# top.net
KiCad netlist of a schematic drawn in Altium Designer
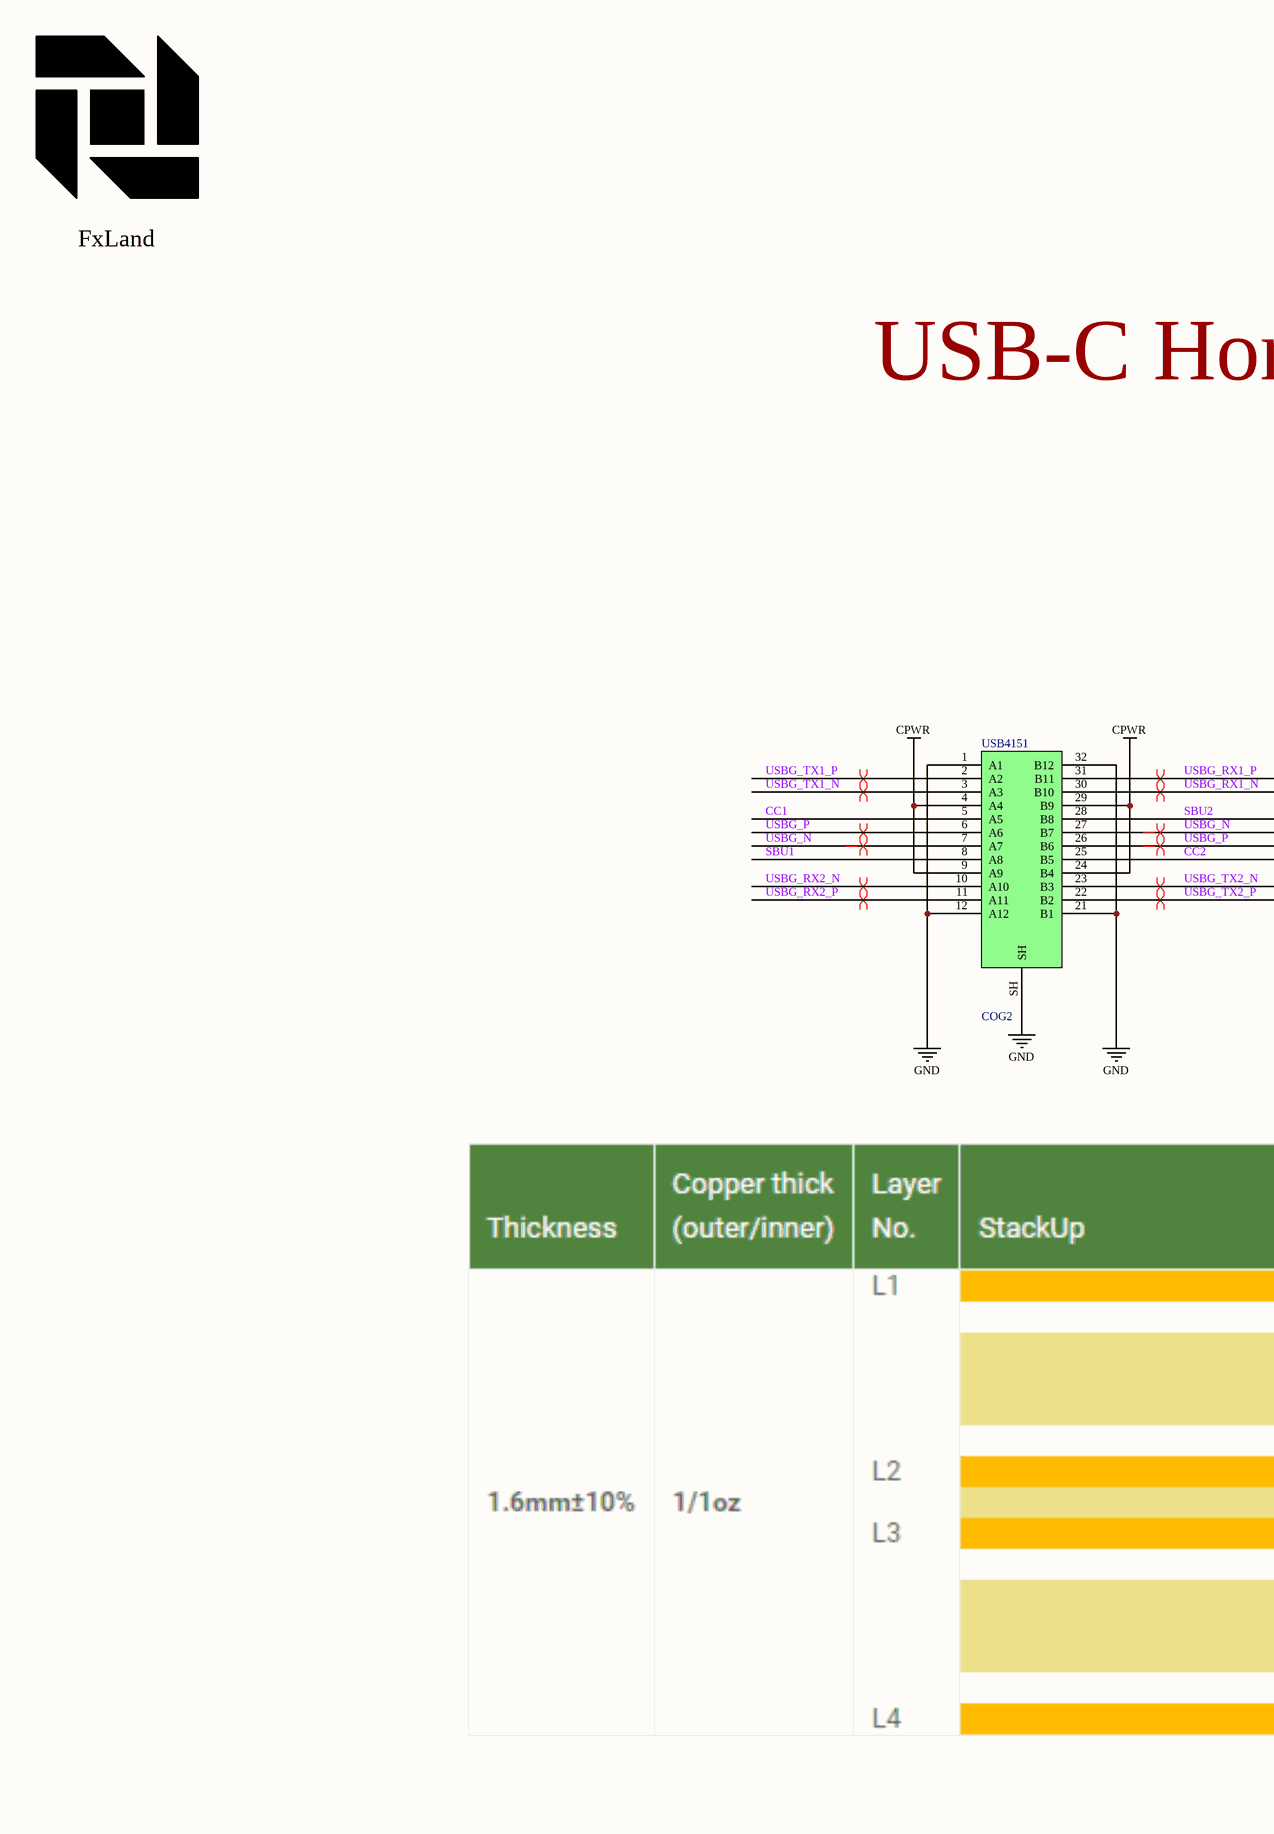
[diagram p0: top.SchDoc, left]
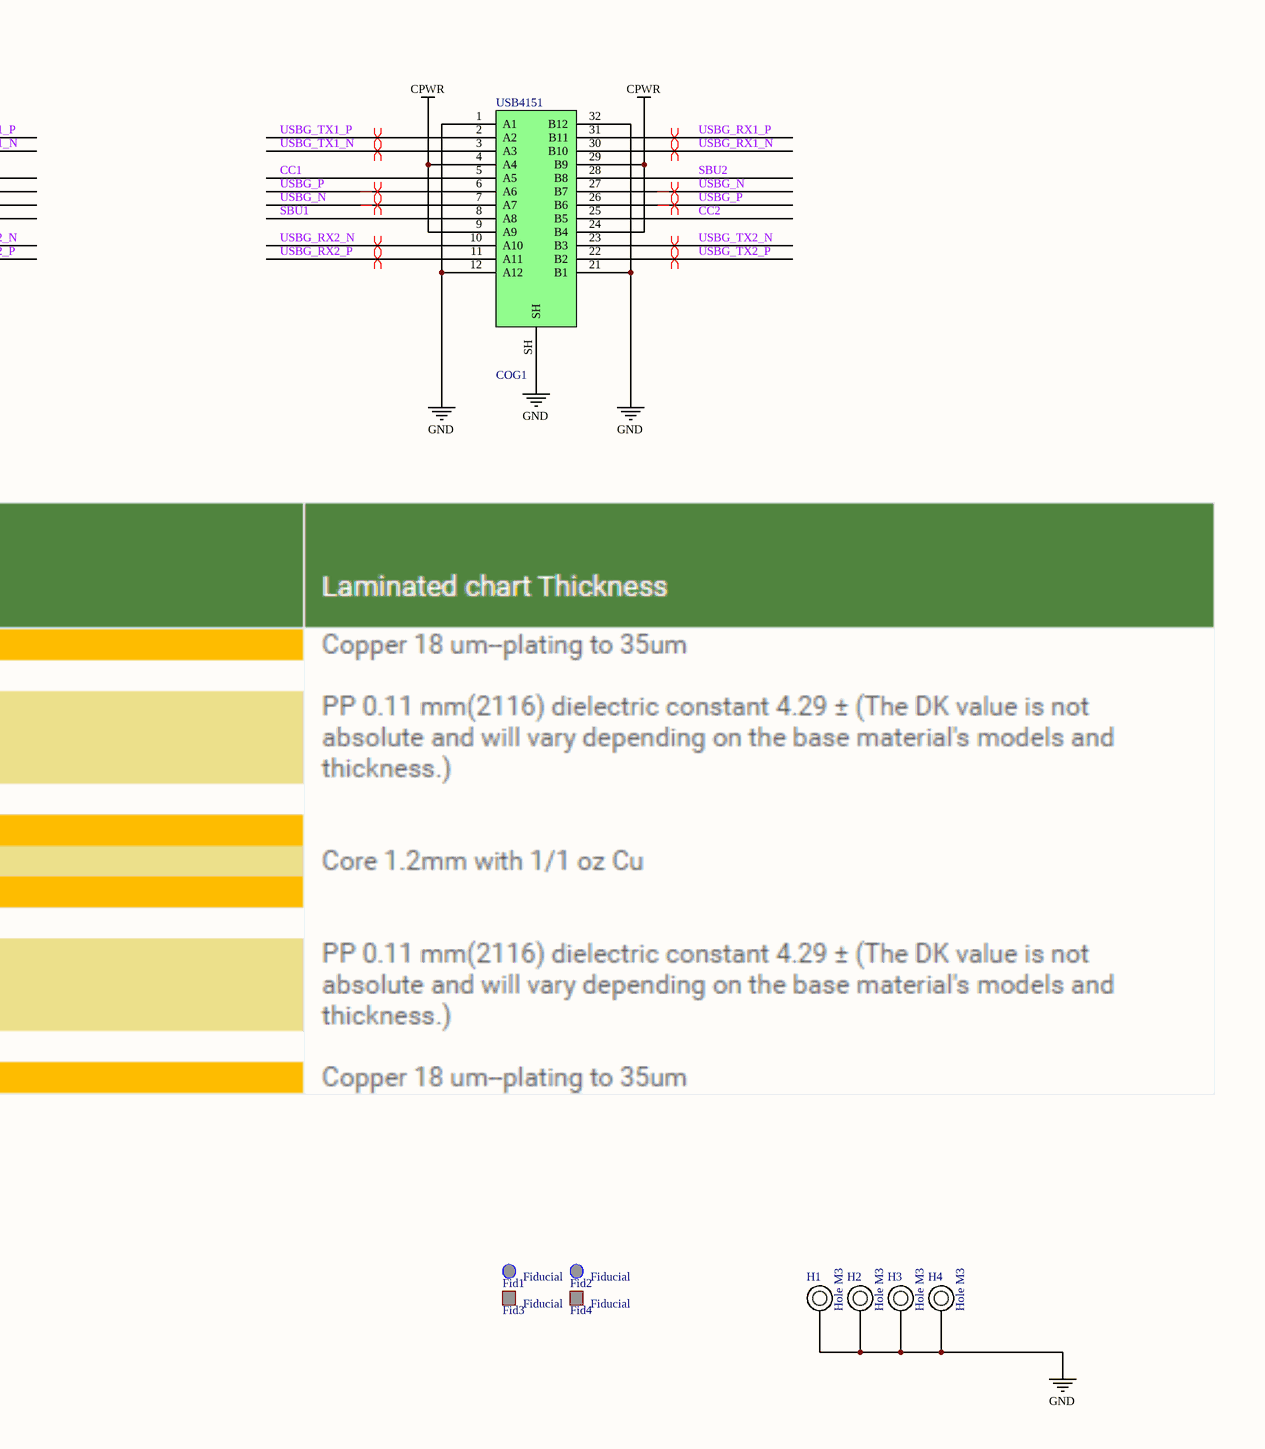
[diagram p1: top.SchDoc, right]

(export (version "E")
  (design (tool "Eeschema 10.0.6"))
  (components
    (comp (ref "COG1")
      (value "USB4151")
      (footprint "USB4151-GF-C")
      (description "USB C connector Plug")
      (fields
        (field (name "REFVAL") "USB4151")
        (field (name "PART NUMBER") "CO0017")
        (field (name "MANFACTPART") "USB4151-GF-C")
      )
      (libsource (lib "GTS_Database") (part "USB-CC"))
    )
    (comp (ref "COG2")
      (value "USB4151")
      (footprint "USB4151-GF-C")
      (description "USB C connector Plug")
      (fields
        (field (name "REFVAL") "USB4151")
        (field (name "PART NUMBER") "CO0017")
        (field (name "MANFACTPART") "USB4151-GF-C")
      )
      (libsource (lib "GTS_Database") (part "USB-CC"))
    )
    (comp (ref "Fid1")
      (value "Fiducial")
      (footprint "FidR_1.0mm")
      (description "Fiducial Round 1mm")
      (fields (field (name "REFVAL") "Fiducial") (field (name "PART NUMBER") "ME0011"))
      (libsource (lib "GTS_Database") (part "FidR_1.0mm"))
    )
    (comp (ref "Fid2")
      (value "Fiducial")
      (footprint "FidR_1.0mm")
      (description "Fiducial Round 1mm")
      (fields (field (name "REFVAL") "Fiducial") (field (name "PART NUMBER") "ME0011"))
      (libsource (lib "GTS_Database") (part "FidR_1.0mm"))
    )
    (comp (ref "Fid3")
      (value "Fiducial")
      (footprint "FidS_1.0mm")
      (description "Fiducial Sqaure 1mm")
      (fields (field (name "REFVAL") "Fiducial") (field (name "PART NUMBER") "ME0012"))
      (libsource (lib "GTS_Database") (part "FidS_1.0mm"))
    )
    (comp (ref "Fid4")
      (value "Fiducial")
      (footprint "FidS_1.0mm")
      (description "Fiducial Sqaure 1mm")
      (fields (field (name "REFVAL") "Fiducial") (field (name "PART NUMBER") "ME0012"))
      (libsource (lib "GTS_Database") (part "FidS_1.0mm"))
    )
    (comp (ref "H1")
      (value "Hole M3")
      (footprint "HOLE_M3")
      (description "Mounting Hole M3")
      (fields (field (name "REFVAL") "Hole M3") (field (name "PART NUMBER") "ME0001"))
      (libsource (lib "GTS_Database") (part "HOLE"))
    )
    (comp (ref "H2")
      (value "Hole M3")
      (footprint "HOLE_M3")
      (description "Mounting Hole M3")
      (fields (field (name "REFVAL") "Hole M3") (field (name "PART NUMBER") "ME0001"))
      (libsource (lib "GTS_Database") (part "HOLE"))
    )
    (comp (ref "H3")
      (value "Hole M3")
      (footprint "HOLE_M3")
      (description "Mounting Hole M3")
      (fields (field (name "REFVAL") "Hole M3") (field (name "PART NUMBER") "ME0001"))
      (libsource (lib "GTS_Database") (part "HOLE"))
    )
    (comp (ref "H4")
      (value "Hole M3")
      (footprint "HOLE_M3")
      (description "Mounting Hole M3")
      (fields (field (name "REFVAL") "Hole M3") (field (name "PART NUMBER") "ME0001"))
      (libsource (lib "GTS_Database") (part "HOLE"))
    )
    (comp (ref "Logo FxLand1")
      (value "FxLand")
      (footprint "Logo_FxLand_3")
      (description "Logo FxLand 3")
      (fields (field (name "PART NUMBER") "ME0008"))
      (libsource (lib "GTS_Database") (part "Logo_FxLand_2"))
    )
  )
  (nets
    (net (code "1") (name "/CC1") (class "Default")
      (node (ref "COG1") (pin "5") (pinfunction "A5_5") (pintype "passive"))
      (node (ref "COG2") (pin "5") (pinfunction "A5_5") (pintype "passive"))
    )
    (net (code "2") (name "/CC2") (class "Default")
      (node (ref "COG1") (pin "25") (pinfunction "B5_25") (pintype "passive"))
      (node (ref "COG2") (pin "25") (pinfunction "B5_25") (pintype "passive"))
    )
    (net (code "3") (name "/SBU1") (class "Default")
      (node (ref "COG1") (pin "8") (pinfunction "A8_8") (pintype "passive"))
      (node (ref "COG2") (pin "8") (pinfunction "A8_8") (pintype "passive"))
    )
    (net (code "4") (name "/SBU2") (class "Default")
      (node (ref "COG1") (pin "28") (pinfunction "B8_28") (pintype "passive"))
      (node (ref "COG2") (pin "28") (pinfunction "B8_28") (pintype "passive"))
    )
    (net (code "5") (name "/USBG_N") (class "Default")
      (node (ref "COG1") (pin "27") (pinfunction "B7_27") (pintype "passive"))
      (node (ref "COG1") (pin "7") (pinfunction "A7_7") (pintype "passive"))
      (node (ref "COG2") (pin "27") (pinfunction "B7_27") (pintype "passive"))
      (node (ref "COG2") (pin "7") (pinfunction "A7_7") (pintype "passive"))
    )
    (net (code "6") (name "/USBG_P") (class "Default")
      (node (ref "COG1") (pin "26") (pinfunction "B6_26") (pintype "passive"))
      (node (ref "COG1") (pin "6") (pinfunction "A6_6") (pintype "passive"))
      (node (ref "COG2") (pin "26") (pinfunction "B6_26") (pintype "passive"))
      (node (ref "COG2") (pin "6") (pinfunction "A6_6") (pintype "passive"))
    )
    (net (code "7") (name "/USBG_RX1_N") (class "Default")
      (node (ref "COG1") (pin "30") (pinfunction "B10_30") (pintype "passive"))
      (node (ref "COG2") (pin "30") (pinfunction "B10_30") (pintype "passive"))
    )
    (net (code "8") (name "/USBG_RX1_P") (class "Default")
      (node (ref "COG1") (pin "31") (pinfunction "B11_31") (pintype "passive"))
      (node (ref "COG2") (pin "31") (pinfunction "B11_31") (pintype "passive"))
    )
    (net (code "9") (name "/USBG_RX2_N") (class "Default")
      (node (ref "COG1") (pin "10") (pinfunction "A10_10") (pintype "passive"))
      (node (ref "COG2") (pin "10") (pinfunction "A10_10") (pintype "passive"))
    )
    (net (code "10") (name "/USBG_RX2_P") (class "Default")
      (node (ref "COG1") (pin "11") (pinfunction "A11_11") (pintype "passive"))
      (node (ref "COG2") (pin "11") (pinfunction "A11_11") (pintype "passive"))
    )
    (net (code "11") (name "/USBG_TX1_N") (class "Default")
      (node (ref "COG1") (pin "3") (pinfunction "A3_3") (pintype "passive"))
      (node (ref "COG2") (pin "3") (pinfunction "A3_3") (pintype "passive"))
    )
    (net (code "12") (name "/USBG_TX1_P") (class "Default")
      (node (ref "COG1") (pin "2") (pinfunction "A2_2") (pintype "passive"))
      (node (ref "COG2") (pin "2") (pinfunction "A2_2") (pintype "passive"))
    )
    (net (code "13") (name "/USBG_TX2_N") (class "Default")
      (node (ref "COG1") (pin "23") (pinfunction "B3_23") (pintype "passive"))
      (node (ref "COG2") (pin "23") (pinfunction "B3_23") (pintype "passive"))
    )
    (net (code "14") (name "/USBG_TX2_P") (class "Default")
      (node (ref "COG1") (pin "22") (pinfunction "B2_22") (pintype "passive"))
      (node (ref "COG2") (pin "22") (pinfunction "B2_22") (pintype "passive"))
    )
    (net (code "15") (name "CPWR") (class "Default")
      (node (ref "COG1") (pin "24") (pinfunction "B4_24") (pintype "passive"))
      (node (ref "COG1") (pin "29") (pinfunction "B9_29") (pintype "passive"))
      (node (ref "COG1") (pin "4") (pinfunction "A4_4") (pintype "passive"))
      (node (ref "COG1") (pin "9") (pinfunction "A9_9") (pintype "passive"))
      (node (ref "COG2") (pin "24") (pinfunction "B4_24") (pintype "passive"))
      (node (ref "COG2") (pin "29") (pinfunction "B9_29") (pintype "passive"))
      (node (ref "COG2") (pin "4") (pinfunction "A4_4") (pintype "passive"))
      (node (ref "COG2") (pin "9") (pinfunction "A9_9") (pintype "passive"))
    )
    (net (code "16") (name "GND") (class "Default")
      (node (ref "COG1") (pin "1") (pinfunction "A1_1") (pintype "passive"))
      (node (ref "COG1") (pin "12") (pinfunction "A12_12") (pintype "passive"))
      (node (ref "COG1") (pin "21") (pinfunction "B1_21") (pintype "passive"))
      (node (ref "COG1") (pin "32") (pinfunction "B12_32") (pintype "passive"))
      (node (ref "COG1") (pin "SH") (pinfunction "SH_SH") (pintype "power_in"))
      (node (ref "COG2") (pin "1") (pinfunction "A1_1") (pintype "passive"))
      (node (ref "COG2") (pin "12") (pinfunction "A12_12") (pintype "passive"))
      (node (ref "COG2") (pin "21") (pinfunction "B1_21") (pintype "passive"))
      (node (ref "COG2") (pin "32") (pinfunction "B12_32") (pintype "passive"))
      (node (ref "COG2") (pin "SH") (pinfunction "SH_SH") (pintype "power_in"))
      (node (ref "H1") (pin "1") (pinfunction "1_1") (pintype "passive"))
      (node (ref "H2") (pin "1") (pinfunction "1_1") (pintype "passive"))
      (node (ref "H3") (pin "1") (pinfunction "1_1") (pintype "passive"))
      (node (ref "H4") (pin "1") (pinfunction "1_1") (pintype "passive"))
    )
  )
)
